# pdbV2_0.net
KiCad netlist of a schematic drawn in EAGLE
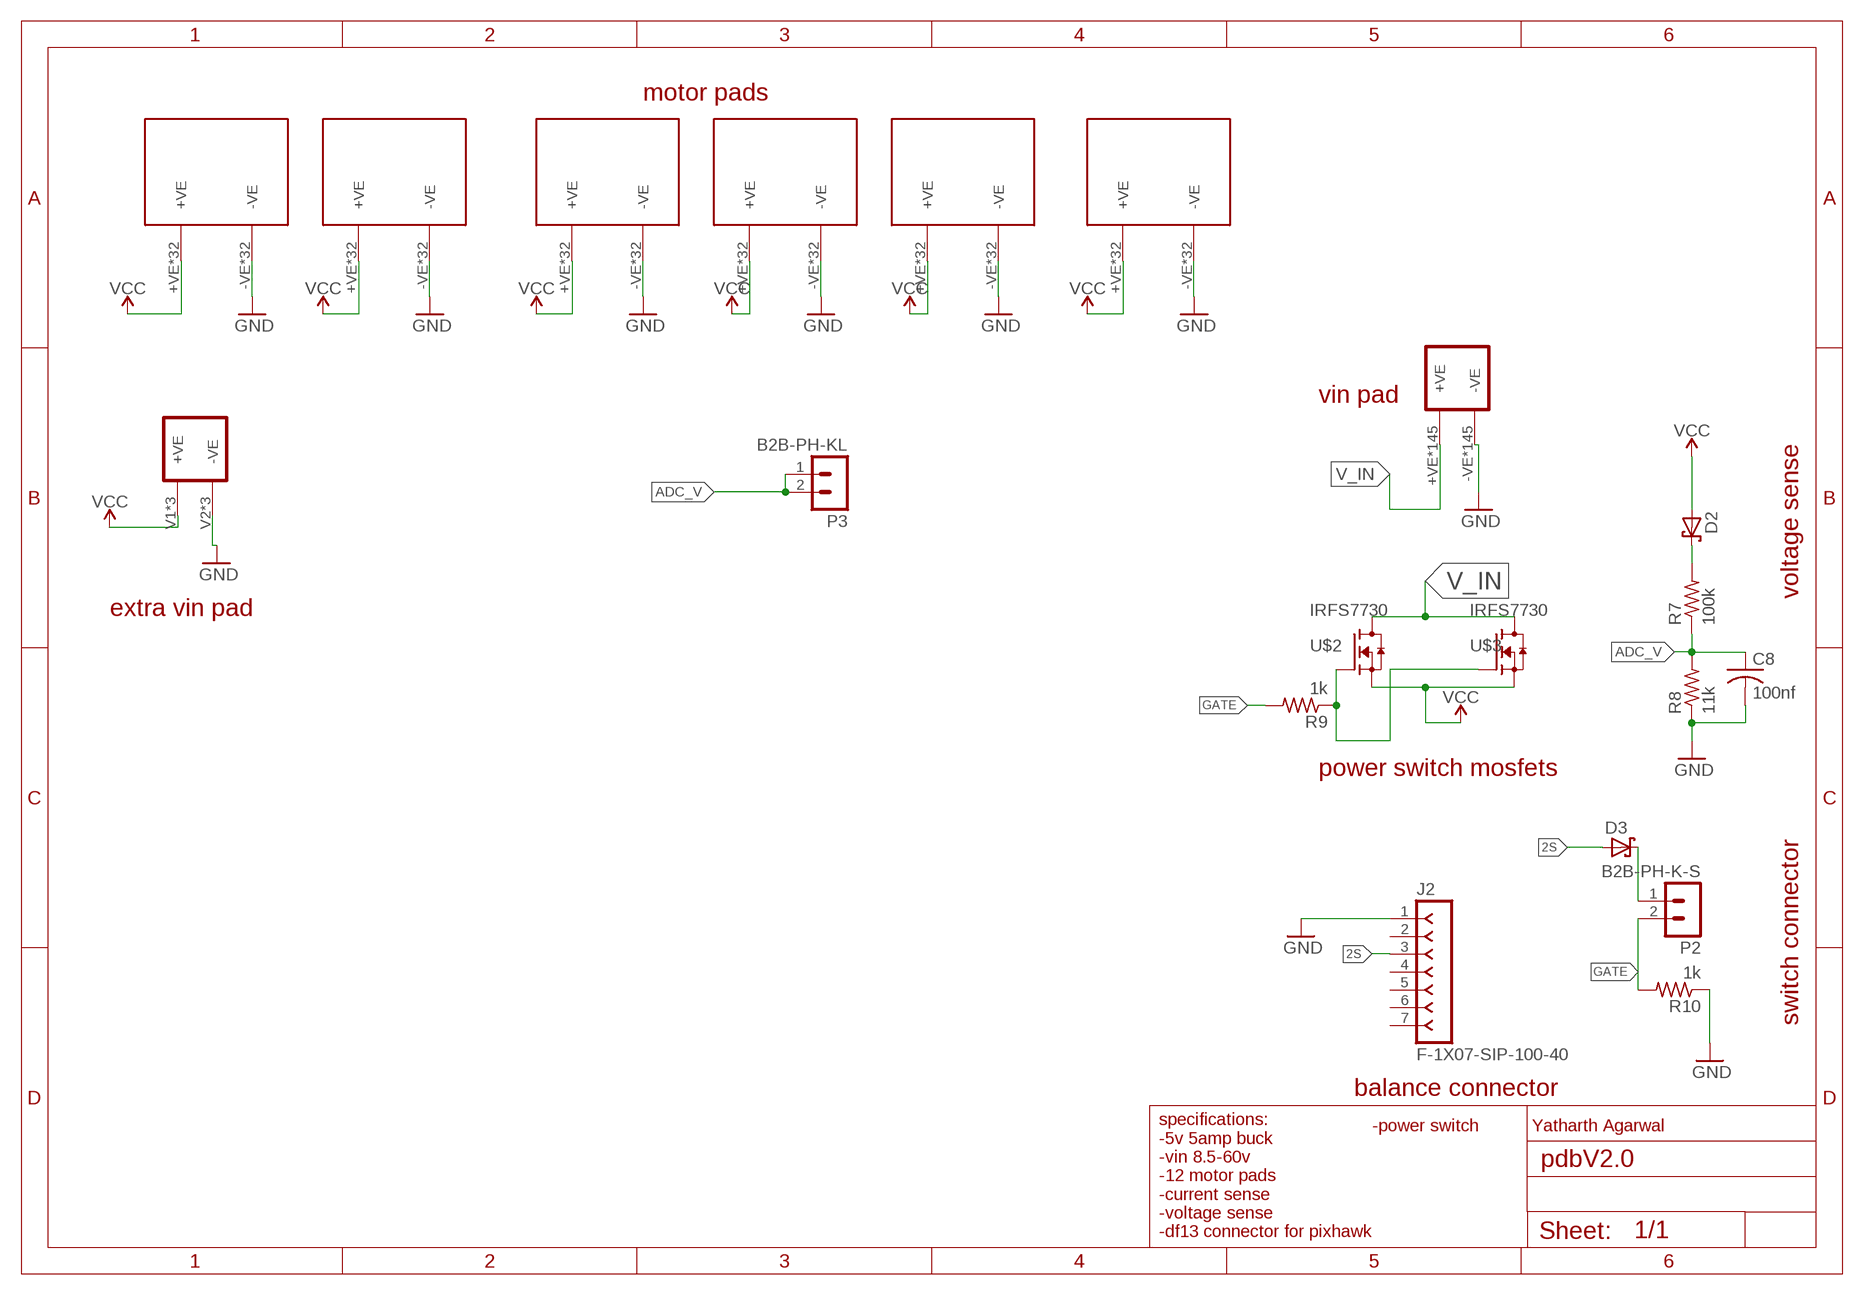
[diagram p0: schematic, sheet 1]

(export (version "E")
  (design (tool "Eeschema 10.0.6"))
  (components
    (comp (ref "C8")
      (value "100nf")
      (footprint "eagle-import:C0805")
      (libsource (lib "eagle-import") (part "C-USC0805"))
    )
    (comp (ref "D2")
      (value "1PS76SB70,115")
      (footprint "eagle-import:SOD323(F)")
      (fields (field (name "MF") "Nexperia USA"))
      (libsource (lib "eagle-import") (part "1PS76SB70,115"))
    )
    (comp (ref "D3")
      (value "1PS76SB70,115")
      (footprint "eagle-import:SOD323(F)")
      (fields (field (name "MF") "Nexperia USA"))
      (libsource (lib "eagle-import") (part "1PS76SB70,115"))
    )
    (comp (ref "J2")
      (value "F-1X07-SIP-100-40")
      (footprint "eagle-import:SIP-100-07-40")
      (libsource (lib "eagle-import") (part "F-1X07-SIP-100-40"))
    )
    (comp (ref "P2")
      (value "B2B-PH-K-S")
      (footprint "eagle-import:B2B-PH-K-S")
      (libsource (lib "eagle-import") (part "B2B-PH-K-S"))
    )
    (comp (ref "P3")
      (value "B2B-PH-KL")
      (footprint "eagle-import:B2B-PH-K-S")
      (libsource (lib "eagle-import") (part "B2B-PH-KL"))
    )
    (comp (ref "R7")
      (value "100k")
      (footprint "eagle-import:R0805")
      (libsource (lib "eagle-import") (part "R-US_R0805"))
    )
    (comp (ref "R8")
      (value "11k")
      (footprint "eagle-import:R0805")
      (libsource (lib "eagle-import") (part "R-US_R0805"))
    )
    (comp (ref "R9")
      (value "1k")
      (footprint "eagle-import:R0805")
      (libsource (lib "eagle-import") (part "R-US_R0805"))
    )
    (comp (ref "R10")
      (value "1k")
      (footprint "eagle-import:R0805")
      (libsource (lib "eagle-import") (part "R-US_R0805"))
    )
    (comp (ref "T1")
      (value "BATTERY_PAD")
      (footprint "eagle-import:BATTERY_PAD")
      (libsource (lib "eagle-import") (part "BATTERY_PAD"))
    )
    (comp (ref "T2")
      (value "MOTOR_PAD")
      (footprint "eagle-import:MOTOR_PAD")
      (libsource (lib "eagle-import") (part "MOTOR_PAD"))
    )
    (comp (ref "T3")
      (value "MOTOR_PAD")
      (footprint "eagle-import:MOTOR_PAD")
      (libsource (lib "eagle-import") (part "MOTOR_PAD"))
    )
    (comp (ref "T4")
      (value "MOTOR_PAD")
      (footprint "eagle-import:MOTOR_PAD")
      (libsource (lib "eagle-import") (part "MOTOR_PAD"))
    )
    (comp (ref "T5")
      (value "MOTOR_PAD")
      (footprint "eagle-import:MOTOR_PAD")
      (libsource (lib "eagle-import") (part "MOTOR_PAD"))
    )
    (comp (ref "T6")
      (value "MOTOR_PAD")
      (footprint "eagle-import:MOTOR_PAD")
      (libsource (lib "eagle-import") (part "MOTOR_PAD"))
    )
    (comp (ref "T7")
      (value "MOTOR_PAD")
      (footprint "eagle-import:MOTOR_PAD")
      (libsource (lib "eagle-import") (part "MOTOR_PAD"))
    )
    (comp (ref "U$1")
      (value "CONPAD")
      (footprint "eagle-import:CONPAD")
      (libsource (lib "eagle-import") (part "CONPAD"))
    )
    (comp (ref "U$2")
      (value "IRFS7730")
      (footprint "eagle-import:TO254P1524X457-3N")
      (libsource (lib "eagle-import") (part "IRFS7730"))
    )
    (comp (ref "U$3")
      (value "IRFS7730")
      (footprint "eagle-import:TO254P1524X457-3N")
      (libsource (lib "eagle-import") (part "IRFS7730"))
    )
  )
  (nets
    (net (code "1") (name "2S") (class "Default")
      (node (ref "D3") (pin "2") (pinfunction "A_2") (pintype "passive"))
      (node (ref "J2") (pin "3") (pinfunction "3_3") (pintype "passive"))
    )
    (net (code "2") (name "ADC_V") (class "Default")
      (node (ref "C8") (pin "1") (pinfunction "1_1") (pintype "passive"))
      (node (ref "P3") (pin "1") (pinfunction "1_1") (pintype "passive"))
      (node (ref "P3") (pin "2") (pinfunction "2_2") (pintype "passive"))
      (node (ref "R7") (pin "1") (pinfunction "1_1") (pintype "passive"))
      (node (ref "R8") (pin "2") (pinfunction "2_2") (pintype "passive"))
    )
    (net (code "3") (name "GATE") (class "Default")
      (node (ref "P2") (pin "2") (pinfunction "2_2") (pintype "passive"))
      (node (ref "R10") (pin "2") (pinfunction "2_2") (pintype "passive"))
      (node (ref "R9") (pin "2") (pinfunction "2_2") (pintype "passive"))
    )
    (net (code "4") (name "GND") (class "Default")
      (node (ref "C8") (pin "2") (pinfunction "2_2") (pintype "passive"))
      (node (ref "J2") (pin "1") (pinfunction "1_1") (pintype "passive"))
      (node (ref "R10") (pin "1") (pinfunction "1_1") (pintype "passive"))
      (node (ref "R8") (pin "1") (pinfunction "1_1") (pintype "passive"))
      (node (ref "T1") (pin "-VE") (pinfunction "-VE_-VE") (pintype "bidirectional"))
      (node (ref "T1") (pin "-VE_1") (pinfunction "-VE_-VE_1") (pintype "bidirectional"))
      (node (ref "T1") (pin "V109") (pinfunction "-VE_V109") (pintype "bidirectional"))
      (node (ref "T1") (pin "V110") (pinfunction "-VE_V110") (pintype "bidirectional"))
      (node (ref "T1") (pin "V111") (pinfunction "-VE_V111") (pintype "bidirectional"))
      (node (ref "T1") (pin "V112") (pinfunction "-VE_V112") (pintype "bidirectional"))
      (node (ref "T1") (pin "V113") (pinfunction "-VE_V113") (pintype "bidirectional"))
      (node (ref "T1") (pin "V114") (pinfunction "-VE_V114") (pintype "bidirectional"))
      (node (ref "T1") (pin "V115") (pinfunction "-VE_V115") (pintype "bidirectional"))
      (node (ref "T1") (pin "V116") (pinfunction "-VE_V116") (pintype "bidirectional"))
      (node (ref "T1") (pin "V117") (pinfunction "-VE_V117") (pintype "bidirectional"))
      (node (ref "T1") (pin "V118") (pinfunction "-VE_V118") (pintype "bidirectional"))
      (node (ref "T1") (pin "V119") (pinfunction "-VE_V119") (pintype "bidirectional"))
      (node (ref "T1") (pin "V121") (pinfunction "-VE_V121") (pintype "bidirectional"))
      (node (ref "T1") (pin "V122") (pinfunction "-VE_V122") (pintype "bidirectional"))
      (node (ref "T1") (pin "V123") (pinfunction "-VE_V123") (pintype "bidirectional"))
      (node (ref "T1") (pin "V124") (pinfunction "-VE_V124") (pintype "bidirectional"))
      (node (ref "T1") (pin "V125") (pinfunction "-VE_V125") (pintype "bidirectional"))
      (node (ref "T1") (pin "V126") (pinfunction "-VE_V126") (pintype "bidirectional"))
      (node (ref "T1") (pin "V127") (pinfunction "-VE_V127") (pintype "bidirectional"))
      (node (ref "T1") (pin "V128") (pinfunction "-VE_V128") (pintype "bidirectional"))
      (node (ref "T1") (pin "V129") (pinfunction "-VE_V129") (pintype "bidirectional"))
      (node (ref "T1") (pin "V130") (pinfunction "-VE_V130") (pintype "bidirectional"))
      (node (ref "T1") (pin "V131") (pinfunction "-VE_V131") (pintype "bidirectional"))
      (node (ref "T1") (pin "V133") (pinfunction "-VE_V133") (pintype "bidirectional"))
      (node (ref "T1") (pin "V134") (pinfunction "-VE_V134") (pintype "bidirectional"))
      (node (ref "T1") (pin "V135") (pinfunction "-VE_V135") (pintype "bidirectional"))
      (node (ref "T1") (pin "V136") (pinfunction "-VE_V136") (pintype "bidirectional"))
      (node (ref "T1") (pin "V137") (pinfunction "-VE_V137") (pintype "bidirectional"))
      (node (ref "T1") (pin "V138") (pinfunction "-VE_V138") (pintype "bidirectional"))
      (node (ref "T1") (pin "V139") (pinfunction "-VE_V139") (pintype "bidirectional"))
      (node (ref "T1") (pin "V140") (pinfunction "-VE_V140") (pintype "bidirectional"))
      (node (ref "T1") (pin "V141") (pinfunction "-VE_V141") (pintype "bidirectional"))
      (node (ref "T1") (pin "V142") (pinfunction "-VE_V142") (pintype "bidirectional"))
      (node (ref "T1") (pin "V143") (pinfunction "-VE_V143") (pintype "bidirectional"))
      (node (ref "T1") (pin "V145") (pinfunction "-VE_V145") (pintype "bidirectional"))
      (node (ref "T1") (pin "V146") (pinfunction "-VE_V146") (pintype "bidirectional"))
      (node (ref "T1") (pin "V147") (pinfunction "-VE_V147") (pintype "bidirectional"))
      (node (ref "T1") (pin "V148") (pinfunction "-VE_V148") (pintype "bidirectional"))
      (node (ref "T1") (pin "V149") (pinfunction "-VE_V149") (pintype "bidirectional"))
      (node (ref "T1") (pin "V150") (pinfunction "-VE_V150") (pintype "bidirectional"))
      (node (ref "T1") (pin "V151") (pinfunction "-VE_V151") (pintype "bidirectional"))
      (node (ref "T1") (pin "V152") (pinfunction "-VE_V152") (pintype "bidirectional"))
      (node (ref "T1") (pin "V153") (pinfunction "-VE_V153") (pintype "bidirectional"))
      (node (ref "T1") (pin "V154") (pinfunction "-VE_V154") (pintype "bidirectional"))
      (node (ref "T1") (pin "V155") (pinfunction "-VE_V155") (pintype "bidirectional"))
      (node (ref "T1") (pin "V157") (pinfunction "-VE_V157") (pintype "bidirectional"))
      (node (ref "T1") (pin "V158") (pinfunction "-VE_V158") (pintype "bidirectional"))
      (node (ref "T1") (pin "V159") (pinfunction "-VE_V159") (pintype "bidirectional"))
      (node (ref "T1") (pin "V160") (pinfunction "-VE_V160") (pintype "bidirectional"))
      (node (ref "T1") (pin "V161") (pinfunction "-VE_V161") (pintype "bidirectional"))
      (node (ref "T1") (pin "V162") (pinfunction "-VE_V162") (pintype "bidirectional"))
      (node (ref "T1") (pin "V163") (pinfunction "-VE_V163") (pintype "bidirectional"))
      (node (ref "T1") (pin "V164") (pinfunction "-VE_V164") (pintype "bidirectional"))
      (node (ref "T1") (pin "V165") (pinfunction "-VE_V165") (pintype "bidirectional"))
      (node (ref "T1") (pin "V166") (pinfunction "-VE_V166") (pintype "bidirectional"))
      (node (ref "T1") (pin "V167") (pinfunction "-VE_V167") (pintype "bidirectional"))
      (node (ref "T1") (pin "V169") (pinfunction "-VE_V169") (pintype "bidirectional"))
      (node (ref "T1") (pin "V170") (pinfunction "-VE_V170") (pintype "bidirectional"))
      (node (ref "T1") (pin "V171") (pinfunction "-VE_V171") (pintype "bidirectional"))
      (node (ref "T1") (pin "V172") (pinfunction "-VE_V172") (pintype "bidirectional"))
      (node (ref "T1") (pin "V173") (pinfunction "-VE_V173") (pintype "bidirectional"))
      (node (ref "T1") (pin "V174") (pinfunction "-VE_V174") (pintype "bidirectional"))
      (node (ref "T1") (pin "V175") (pinfunction "-VE_V175") (pintype "bidirectional"))
      (node (ref "T1") (pin "V176") (pinfunction "-VE_V176") (pintype "bidirectional"))
      (node (ref "T1") (pin "V177") (pinfunction "-VE_V177") (pintype "bidirectional"))
      (node (ref "T1") (pin "V178") (pinfunction "-VE_V178") (pintype "bidirectional"))
      (node (ref "T1") (pin "V179") (pinfunction "-VE_V179") (pintype "bidirectional"))
      (node (ref "T1") (pin "V181") (pinfunction "-VE_V181") (pintype "bidirectional"))
      (node (ref "T1") (pin "V182") (pinfunction "-VE_V182") (pintype "bidirectional"))
      (node (ref "T1") (pin "V183") (pinfunction "-VE_V183") (pintype "bidirectional"))
      (node (ref "T1") (pin "V184") (pinfunction "-VE_V184") (pintype "bidirectional"))
      (node (ref "T1") (pin "V185") (pinfunction "-VE_V185") (pintype "bidirectional"))
      (node (ref "T1") (pin "V186") (pinfunction "-VE_V186") (pintype "bidirectional"))
      (node (ref "T1") (pin "V187") (pinfunction "-VE_V187") (pintype "bidirectional"))
      (node (ref "T1") (pin "V188") (pinfunction "-VE_V188") (pintype "bidirectional"))
      (node (ref "T1") (pin "V189") (pinfunction "-VE_V189") (pintype "bidirectional"))
      (node (ref "T1") (pin "V190") (pinfunction "-VE_V190") (pintype "bidirectional"))
      (node (ref "T1") (pin "V191") (pinfunction "-VE_V191") (pintype "bidirectional"))
      (node (ref "T1") (pin "V193") (pinfunction "-VE_V193") (pintype "bidirectional"))
      (node (ref "T1") (pin "V194") (pinfunction "-VE_V194") (pintype "bidirectional"))
      (node (ref "T1") (pin "V195") (pinfunction "-VE_V195") (pintype "bidirectional"))
      (node (ref "T1") (pin "V196") (pinfunction "-VE_V196") (pintype "bidirectional"))
      (node (ref "T1") (pin "V197") (pinfunction "-VE_V197") (pintype "bidirectional"))
      (node (ref "T1") (pin "V198") (pinfunction "-VE_V198") (pintype "bidirectional"))
      (node (ref "T1") (pin "V199") (pinfunction "-VE_V199") (pintype "bidirectional"))
      (node (ref "T1") (pin "V200") (pinfunction "-VE_V200") (pintype "bidirectional"))
      (node (ref "T1") (pin "V201") (pinfunction "-VE_V201") (pintype "bidirectional"))
      (node (ref "T1") (pin "V202") (pinfunction "-VE_V202") (pintype "bidirectional"))
      (node (ref "T1") (pin "V203") (pinfunction "-VE_V203") (pintype "bidirectional"))
      (node (ref "T1") (pin "V232") (pinfunction "-VE_V232") (pintype "bidirectional"))
      (node (ref "T1") (pin "V233") (pinfunction "-VE_V233") (pintype "bidirectional"))
      (node (ref "T1") (pin "V234") (pinfunction "-VE_V234") (pintype "bidirectional"))
      (node (ref "T1") (pin "V235") (pinfunction "-VE_V235") (pintype "bidirectional"))
      (node (ref "T1") (pin "V236") (pinfunction "-VE_V236") (pintype "bidirectional"))
      (node (ref "T1") (pin "V237") (pinfunction "-VE_V237") (pintype "bidirectional"))
      (node (ref "T1") (pin "V238") (pinfunction "-VE_V238") (pintype "bidirectional"))
      (node (ref "T1") (pin "V239") (pinfunction "-VE_V239") (pintype "bidirectional"))
      (node (ref "T1") (pin "V240") (pinfunction "-VE_V240") (pintype "bidirectional"))
      (node (ref "T1") (pin "V241") (pinfunction "-VE_V241") (pintype "bidirectional"))
      (node (ref "T1") (pin "V242") (pinfunction "-VE_V242") (pintype "bidirectional"))
      (node (ref "T1") (pin "V243") (pinfunction "-VE_V243") (pintype "bidirectional"))
      (node (ref "T1") (pin "V244") (pinfunction "-VE_V244") (pintype "bidirectional"))
      (node (ref "T1") (pin "V245") (pinfunction "-VE_V245") (pintype "bidirectional"))
      (node (ref "T1") (pin "V246") (pinfunction "-VE_V246") (pintype "bidirectional"))
      (node (ref "T1") (pin "V247") (pinfunction "-VE_V247") (pintype "bidirectional"))
      (node (ref "T1") (pin "V248") (pinfunction "-VE_V248") (pintype "bidirectional"))
      (node (ref "T1") (pin "V249") (pinfunction "-VE_V249") (pintype "bidirectional"))
      (node (ref "T1") (pin "V250") (pinfunction "-VE_V250") (pintype "bidirectional"))
      (node (ref "T1") (pin "V251") (pinfunction "-VE_V251") (pintype "bidirectional"))
      (node (ref "T1") (pin "V252") (pinfunction "-VE_V252") (pintype "bidirectional"))
      (node (ref "T1") (pin "V253") (pinfunction "-VE_V253") (pintype "bidirectional"))
      (node (ref "T1") (pin "V254") (pinfunction "-VE_V254") (pintype "bidirectional"))
      (node (ref "T1") (pin "V255") (pinfunction "-VE_V255") (pintype "bidirectional"))
      (node (ref "T1") (pin "V256") (pinfunction "-VE_V256") (pintype "bidirectional"))
      (node (ref "T1") (pin "V257") (pinfunction "-VE_V257") (pintype "bidirectional"))
      (node (ref "T1") (pin "V258") (pinfunction "-VE_V258") (pintype "bidirectional"))
      (node (ref "T1") (pin "V259") (pinfunction "-VE_V259") (pintype "bidirectional"))
      (node (ref "T1") (pin "V260") (pinfunction "-VE_V260") (pintype "bidirectional"))
      (node (ref "T1") (pin "V261") (pinfunction "-VE_V261") (pintype "bidirectional"))
      (node (ref "T1") (pin "V262") (pinfunction "-VE_V262") (pintype "bidirectional"))
      (node (ref "T1") (pin "V263") (pinfunction "-VE_V263") (pintype "bidirectional"))
      (node (ref "T1") (pin "V264") (pinfunction "-VE_V264") (pintype "bidirectional"))
      (node (ref "T1") (pin "V265") (pinfunction "-VE_V265") (pintype "bidirectional"))
      (node (ref "T1") (pin "V266") (pinfunction "-VE_V266") (pintype "bidirectional"))
      (node (ref "T1") (pin "V267") (pinfunction "-VE_V267") (pintype "bidirectional"))
      (node (ref "T1") (pin "V268") (pinfunction "-VE_V268") (pintype "bidirectional"))
      (node (ref "T1") (pin "V269") (pinfunction "-VE_V269") (pintype "bidirectional"))
      (node (ref "T1") (pin "V270") (pinfunction "-VE_V270") (pintype "bidirectional"))
      (node (ref "T1") (pin "V271") (pinfunction "-VE_V271") (pintype "bidirectional"))
      (node (ref "T1") (pin "V272") (pinfunction "-VE_V272") (pintype "bidirectional"))
      (node (ref "T1") (pin "V273") (pinfunction "-VE_V273") (pintype "bidirectional"))
      (node (ref "T1") (pin "V274") (pinfunction "-VE_V274") (pintype "bidirectional"))
      (node (ref "T1") (pin "V275") (pinfunction "-VE_V275") (pintype "bidirectional"))
      (node (ref "T1") (pin "V276") (pinfunction "-VE_V276") (pintype "bidirectional"))
      (node (ref "T1") (pin "V277") (pinfunction "-VE_V277") (pintype "bidirectional"))
      (node (ref "T1") (pin "V278") (pinfunction "-VE_V278") (pintype "bidirectional"))
      (node (ref "T1") (pin "V279") (pinfunction "-VE_V279") (pintype "bidirectional"))
      (node (ref "T1") (pin "V280") (pinfunction "-VE_V280") (pintype "bidirectional"))
      (node (ref "T1") (pin "V281") (pinfunction "-VE_V281") (pintype "bidirectional"))
      (node (ref "T1") (pin "V282") (pinfunction "-VE_V282") (pintype "bidirectional"))
      (node (ref "T1") (pin "V283") (pinfunction "-VE_V283") (pintype "bidirectional"))
      (node (ref "T1") (pin "V284") (pinfunction "-VE_V284") (pintype "bidirectional"))
      (node (ref "T1") (pin "V285") (pinfunction "-VE_V285") (pintype "bidirectional"))
      (node (ref "T1") (pin "V286") (pinfunction "-VE_V286") (pintype "bidirectional"))
      (node (ref "T2") (pin "-VE") (pinfunction "-VE_-VE") (pintype "output"))
      (node (ref "T2") (pin "-VE_1") (pinfunction "-VE_-VE_1") (pintype "output"))
      (node (ref "T2") (pin "V32") (pinfunction "-VE_V32") (pintype "output"))
      (node (ref "T2") (pin "V33") (pinfunction "-VE_V33") (pintype "output"))
      (node (ref "T2") (pin "V34") (pinfunction "-VE_V34") (pintype "output"))
      (node (ref "T2") (pin "V35") (pinfunction "-VE_V35") (pintype "output"))
      (node (ref "T2") (pin "V36") (pinfunction "-VE_V36") (pintype "output"))
      (node (ref "T2") (pin "V37") (pinfunction "-VE_V37") (pintype "output"))
      (node (ref "T2") (pin "V38") (pinfunction "-VE_V38") (pintype "output"))
      (node (ref "T2") (pin "V39") (pinfunction "-VE_V39") (pintype "output"))
      (node (ref "T2") (pin "V40") (pinfunction "-VE_V40") (pintype "output"))
      (node (ref "T2") (pin "V41") (pinfunction "-VE_V41") (pintype "output"))
      (node (ref "T2") (pin "V42") (pinfunction "-VE_V42") (pintype "output"))
      (node (ref "T2") (pin "V43") (pinfunction "-VE_V43") (pintype "output"))
      (node (ref "T2") (pin "V44") (pinfunction "-VE_V44") (pintype "output"))
      (node (ref "T2") (pin "V45") (pinfunction "-VE_V45") (pintype "output"))
      (node (ref "T2") (pin "V46") (pinfunction "-VE_V46") (pintype "output"))
      (node (ref "T2") (pin "V47") (pinfunction "-VE_V47") (pintype "output"))
      (node (ref "T2") (pin "V48") (pinfunction "-VE_V48") (pintype "output"))
      (node (ref "T2") (pin "V49") (pinfunction "-VE_V49") (pintype "output"))
      (node (ref "T2") (pin "V50") (pinfunction "-VE_V50") (pintype "output"))
      (node (ref "T2") (pin "V51") (pinfunction "-VE_V51") (pintype "output"))
      (node (ref "T2") (pin "V52") (pinfunction "-VE_V52") (pintype "output"))
      (node (ref "T2") (pin "V53") (pinfunction "-VE_V53") (pintype "output"))
      (node (ref "T2") (pin "V54") (pinfunction "-VE_V54") (pintype "output"))
      (node (ref "T2") (pin "V55") (pinfunction "-VE_V55") (pintype "output"))
      (node (ref "T2") (pin "V56") (pinfunction "-VE_V56") (pintype "output"))
      (node (ref "T2") (pin "V57") (pinfunction "-VE_V57") (pintype "output"))
      (node (ref "T2") (pin "V58") (pinfunction "-VE_V58") (pintype "output"))
      (node (ref "T2") (pin "V59") (pinfunction "-VE_V59") (pintype "output"))
      (node (ref "T2") (pin "V60") (pinfunction "-VE_V60") (pintype "output"))
      (node (ref "T2") (pin "V61") (pinfunction "-VE_V61") (pintype "output"))
      (node (ref "T3") (pin "-VE") (pinfunction "-VE_-VE") (pintype "output"))
      (node (ref "T3") (pin "-VE_1") (pinfunction "-VE_-VE_1") (pintype "output"))
      (node (ref "T3") (pin "V32") (pinfunction "-VE_V32") (pintype "output"))
      (node (ref "T3") (pin "V33") (pinfunction "-VE_V33") (pintype "output"))
      (node (ref "T3") (pin "V34") (pinfunction "-VE_V34") (pintype "output"))
      (node (ref "T3") (pin "V35") (pinfunction "-VE_V35") (pintype "output"))
      (node (ref "T3") (pin "V36") (pinfunction "-VE_V36") (pintype "output"))
      (node (ref "T3") (pin "V37") (pinfunction "-VE_V37") (pintype "output"))
      (node (ref "T3") (pin "V38") (pinfunction "-VE_V38") (pintype "output"))
      (node (ref "T3") (pin "V39") (pinfunction "-VE_V39") (pintype "output"))
      (node (ref "T3") (pin "V40") (pinfunction "-VE_V40") (pintype "output"))
      (node (ref "T3") (pin "V41") (pinfunction "-VE_V41") (pintype "output"))
      (node (ref "T3") (pin "V42") (pinfunction "-VE_V42") (pintype "output"))
      (node (ref "T3") (pin "V43") (pinfunction "-VE_V43") (pintype "output"))
      (node (ref "T3") (pin "V44") (pinfunction "-VE_V44") (pintype "output"))
      (node (ref "T3") (pin "V45") (pinfunction "-VE_V45") (pintype "output"))
      (node (ref "T3") (pin "V46") (pinfunction "-VE_V46") (pintype "output"))
      (node (ref "T3") (pin "V47") (pinfunction "-VE_V47") (pintype "output"))
      (node (ref "T3") (pin "V48") (pinfunction "-VE_V48") (pintype "output"))
      (node (ref "T3") (pin "V49") (pinfunction "-VE_V49") (pintype "output"))
      (node (ref "T3") (pin "V50") (pinfunction "-VE_V50") (pintype "output"))
      (node (ref "T3") (pin "V51") (pinfunction "-VE_V51") (pintype "output"))
      (node (ref "T3") (pin "V52") (pinfunction "-VE_V52") (pintype "output"))
      (node (ref "T3") (pin "V53") (pinfunction "-VE_V53") (pintype "output"))
      (node (ref "T3") (pin "V54") (pinfunction "-VE_V54") (pintype "output"))
      (node (ref "T3") (pin "V55") (pinfunction "-VE_V55") (pintype "output"))
      (node (ref "T3") (pin "V56") (pinfunction "-VE_V56") (pintype "output"))
      (node (ref "T3") (pin "V57") (pinfunction "-VE_V57") (pintype "output"))
      (node (ref "T3") (pin "V58") (pinfunction "-VE_V58") (pintype "output"))
      (node (ref "T3") (pin "V59") (pinfunction "-VE_V59") (pintype "output"))
      (node (ref "T3") (pin "V60") (pinfunction "-VE_V60") (pintype "output"))
      (node (ref "T3") (pin "V61") (pinfunction "-VE_V61") (pintype "output"))
      (node (ref "T4") (pin "-VE") (pinfunction "-VE_-VE") (pintype "output"))
      (node (ref "T4") (pin "-VE_1") (pinfunction "-VE_-VE_1") (pintype "output"))
      (node (ref "T4") (pin "V32") (pinfunction "-VE_V32") (pintype "output"))
      (node (ref "T4") (pin "V33") (pinfunction "-VE_V33") (pintype "output"))
      (node (ref "T4") (pin "V34") (pinfunction "-VE_V34") (pintype "output"))
      (node (ref "T4") (pin "V35") (pinfunction "-VE_V35") (pintype "output"))
      (node (ref "T4") (pin "V36") (pinfunction "-VE_V36") (pintype "output"))
      (node (ref "T4") (pin "V37") (pinfunction "-VE_V37") (pintype "output"))
      (node (ref "T4") (pin "V38") (pinfunction "-VE_V38") (pintype "output"))
      (node (ref "T4") (pin "V39") (pinfunction "-VE_V39") (pintype "output"))
      (node (ref "T4") (pin "V40") (pinfunction "-VE_V40") (pintype "output"))
      (node (ref "T4") (pin "V41") (pinfunction "-VE_V41") (pintype "output"))
      (node (ref "T4") (pin "V42") (pinfunction "-VE_V42") (pintype "output"))
      (node (ref "T4") (pin "V43") (pinfunction "-VE_V43") (pintype "output"))
      (node (ref "T4") (pin "V44") (pinfunction "-VE_V44") (pintype "output"))
      (node (ref "T4") (pin "V45") (pinfunction "-VE_V45") (pintype "output"))
      (node (ref "T4") (pin "V46") (pinfunction "-VE_V46") (pintype "output"))
      (node (ref "T4") (pin "V47") (pinfunction "-VE_V47") (pintype "output"))
      (node (ref "T4") (pin "V48") (pinfunction "-VE_V48") (pintype "output"))
      (node (ref "T4") (pin "V49") (pinfunction "-VE_V49") (pintype "output"))
      (node (ref "T4") (pin "V50") (pinfunction "-VE_V50") (pintype "output"))
      (node (ref "T4") (pin "V51") (pinfunction "-VE_V51") (pintype "output"))
      (node (ref "T4") (pin "V52") (pinfunction "-VE_V52") (pintype "output"))
      (node (ref "T4") (pin "V53") (pinfunction "-VE_V53") (pintype "output"))
      (node (ref "T4") (pin "V54") (pinfunction "-VE_V54") (pintype "output"))
      (node (ref "T4") (pin "V55") (pinfunction "-VE_V55") (pintype "output"))
      (node (ref "T4") (pin "V56") (pinfunction "-VE_V56") (pintype "output"))
      (node (ref "T4") (pin "V57") (pinfunction "-VE_V57") (pintype "output"))
      (node (ref "T4") (pin "V58") (pinfunction "-VE_V58") (pintype "output"))
      (node (ref "T4") (pin "V59") (pinfunction "-VE_V59") (pintype "output"))
      (node (ref "T4") (pin "V60") (pinfunction "-VE_V60") (pintype "output"))
      (node (ref "T4") (pin "V61") (pinfunction "-VE_V61") (pintype "output"))
      (node (ref "T5") (pin "-VE") (pinfunction "-VE_-VE") (pintype "output"))
      (node (ref "T5") (pin "-VE_1") (pinfunction "-VE_-VE_1") (pintype "output"))
      (node (ref "T5") (pin "V32") (pinfunction "-VE_V32") (pintype "output"))
      (node (ref "T5") (pin "V33") (pinfunction "-VE_V33") (pintype "output"))
      (node (ref "T5") (pin "V34") (pinfunction "-VE_V34") (pintype "output"))
      (node (ref "T5") (pin "V35") (pinfunction "-VE_V35") (pintype "output"))
      (node (ref "T5") (pin "V36") (pinfunction "-VE_V36") (pintype "output"))
      (node (ref "T5") (pin "V37") (pinfunction "-VE_V37") (pintype "output"))
      (node (ref "T5") (pin "V38") (pinfunction "-VE_V38") (pintype "output"))
      (node (ref "T5") (pin "V39") (pinfunction "-VE_V39") (pintype "output"))
      (node (ref "T5") (pin "V40") (pinfunction "-VE_V40") (pintype "output"))
      (node (ref "T5") (pin "V41") (pinfunction "-VE_V41") (pintype "output"))
      (node (ref "T5") (pin "V42") (pinfunction "-VE_V42") (pintype "output"))
      (node (ref "T5") (pin "V43") (pinfunction "-VE_V43") (pintype "output"))
      (node (ref "T5") (pin "V44") (pinfunction "-VE_V44") (pintype "output"))
      (node (ref "T5") (pin "V45") (pinfunction "-VE_V45") (pintype "output"))
      (node (ref "T5") (pin "V46") (pinfunction "-VE_V46") (pintype "output"))
      (node (ref "T5") (pin "V47") (pinfunction "-VE_V47") (pintype "output"))
      (node (ref "T5") (pin "V48") (pinfunction "-VE_V48") (pintype "output"))
      (node (ref "T5") (pin "V49") (pinfunction "-VE_V49") (pintype "output"))
      (node (ref "T5") (pin "V50") (pinfunction "-VE_V50") (pintype "output"))
      (node (ref "T5") (pin "V51") (pinfunction "-VE_V51") (pintype "output"))
      (node (ref "T5") (pin "V52") (pinfunction "-VE_V52") (pintype "output"))
      (node (ref "T5") (pin "V53") (pinfunction "-VE_V53") (pintype "output"))
      (node (ref "T5") (pin "V54") (pinfunction "-VE_V54") (pintype "output"))
      (node (ref "T5") (pin "V55") (pinfunction "-VE_V55") (pintype "output"))
      (node (ref "T5") (pin "V56") (pinfunction "-VE_V56") (pintype "output"))
      (node (ref "T5") (pin "V57") (pinfunction "-VE_V57") (pintype "output"))
      (node (ref "T5") (pin "V58") (pinfunction "-VE_V58") (pintype "output"))
      (node (ref "T5") (pin "V59") (pinfunction "-VE_V59") (pintype "output"))
      (node (ref "T5") (pin "V60") (pinfunction "-VE_V60") (pintype "output"))
      (node (ref "T5") (pin "V61") (pinfunction "-VE_V61") (pintype "output"))
      (node (ref "T6") (pin "-VE") (pinfunction "-VE_-VE") (pintype "output"))
      (node (ref "T6") (pin "-VE_1") (pinfunction "-VE_-VE_1") (pintype "output"))
      (node (ref "T6") (pin "V32") (pinfunction "-VE_V32") (pintype "output"))
      (node (ref "T6") (pin "V33") (pinfunction "-VE_V33") (pintype "output"))
      (node (ref "T6") (pin "V34") (pinfunction "-VE_V34") (pintype "output"))
      (node (ref "T6") (pin "V35") (pinfunction "-VE_V35") (pintype "output"))
      (node (ref "T6") (pin "V36") (pinfunction "-VE_V36") (pintype "output"))
      (node (ref "T6") (pin "V37") (pinfunction "-VE_V37") (pintype "output"))
      (node (ref "T6") (pin "V38") (pinfunction "-VE_V38") (pintype "output"))
      (node (ref "T6") (pin "V39") (pinfunction "-VE_V39") (pintype "output"))
      (node (ref "T6") (pin "V40") (pinfunction "-VE_V40") (pintype "output"))
      (node (ref "T6") (pin "V41") (pinfunction "-VE_V41") (pintype "output"))
      (node (ref "T6") (pin "V42") (pinfunction "-VE_V42") (pintype "output"))
      (node (ref "T6") (pin "V43") (pinfunction "-VE_V43") (pintype "output"))
      (node (ref "T6") (pin "V44") (pinfunction "-VE_V44") (pintype "output"))
      (node (ref "T6") (pin "V45") (pinfunction "-VE_V45") (pintype "output"))
      (node (ref "T6") (pin "V46") (pinfunction "-VE_V46") (pintype "output"))
      (node (ref "T6") (pin "V47") (pinfunction "-VE_V47") (pintype "output"))
      (node (ref "T6") (pin "V48") (pinfunction "-VE_V48") (pintype "output"))
      (node (ref "T6") (pin "V49") (pinfunction "-VE_V49") (pintype "output"))
      (node (ref "T6") (pin "V50") (pinfunction "-VE_V50") (pintype "output"))
      (node (ref "T6") (pin "V51") (pinfunction "-VE_V51") (pintype "output"))
      (node (ref "T6") (pin "V52") (pinfunction "-VE_V52") (pintype "output"))
      (node (ref "T6") (pin "V53") (pinfunction "-VE_V53") (pintype "output"))
      (node (ref "T6") (pin "V54") (pinfunction "-VE_V54") (pintype "output"))
      (node (ref "T6") (pin "V55") (pinfunction "-VE_V55") (pintype "output"))
      (node (ref "T6") (pin "V56") (pinfunction "-VE_V56") (pintype "output"))
      (node (ref "T6") (pin "V57") (pinfunction "-VE_V57") (pintype "output"))
      (node (ref "T6") (pin "V58") (pinfunction "-VE_V58") (pintype "output"))
      (node (ref "T6") (pin "V59") (pinfunction "-VE_V59") (pintype "output"))
      (node (ref "T6") (pin "V60") (pinfunction "-VE_V60") (pintype "output"))
      (node (ref "T6") (pin "V61") (pinfunction "-VE_V61") (pintype "output"))
      (node (ref "T7") (pin "-VE") (pinfunction "-VE_-VE") (pintype "output"))
      (node (ref "T7") (pin "-VE_1") (pinfunction "-VE_-VE_1") (pintype "output"))
      (node (ref "T7") (pin "V32") (pinfunction "-VE_V32") (pintype "output"))
      (node (ref "T7") (pin "V33") (pinfunction "-VE_V33") (pintype "output"))
      (node (ref "T7") (pin "V34") (pinfunction "-VE_V34") (pintype "output"))
      (node (ref "T7") (pin "V35") (pinfunction "-VE_V35") (pintype "output"))
      (node (ref "T7") (pin "V36") (pinfunction "-VE_V36") (pintype "output"))
      (node (ref "T7") (pin "V37") (pinfunction "-VE_V37") (pintype "output"))
      (node (ref "T7") (pin "V38") (pinfunction "-VE_V38") (pintype "output"))
      (node (ref "T7") (pin "V39") (pinfunction "-VE_V39") (pintype "output"))
      (node (ref "T7") (pin "V40") (pinfunction "-VE_V40") (pintype "output"))
      (node (ref "T7") (pin "V41") (pinfunction "-VE_V41") (pintype "output"))
      (node (ref "T7") (pin "V42") (pinfunction "-VE_V42") (pintype "output"))
      (node (ref "T7") (pin "V43") (pinfunction "-VE_V43") (pintype "output"))
      (node (ref "T7") (pin "V44") (pinfunction "-VE_V44") (pintype "output"))
      (node (ref "T7") (pin "V45") (pinfunction "-VE_V45") (pintype "output"))
      (node (ref "T7") (pin "V46") (pinfunction "-VE_V46") (pintype "output"))
      (node (ref "T7") (pin "V47") (pinfunction "-VE_V47") (pintype "output"))
      (node (ref "T7") (pin "V48") (pinfunction "-VE_V48") (pintype "output"))
      (node (ref "T7") (pin "V49") (pinfunction "-VE_V49") (pintype "output"))
      (node (ref "T7") (pin "V50") (pinfunction "-VE_V50") (pintype "output"))
      (node (ref "T7") (pin "V51") (pinfunction "-VE_V51") (pintype "output"))
      (node (ref "T7") (pin "V52") (pinfunction "-VE_V52") (pintype "output"))
      (node (ref "T7") (pin "V53") (pinfunction "-VE_V53") (pintype "output"))
      (node (ref "T7") (pin "V54") (pinfunction "-VE_V54") (pintype "output"))
      (node (ref "T7") (pin "V55") (pinfunction "-VE_V55") (pintype "output"))
      (node (ref "T7") (pin "V56") (pinfunction "-VE_V56") (pintype "output"))
      (node (ref "T7") (pin "V57") (pinfunction "-VE_V57") (pintype "output"))
      (node (ref "T7") (pin "V58") (pinfunction "-VE_V58") (pintype "output"))
      (node (ref "T7") (pin "V59") (pinfunction "-VE_V59") (pintype "output"))
      (node (ref "T7") (pin "V60") (pinfunction "-VE_V60") (pintype "output"))
      (node (ref "T7") (pin "V61") (pinfunction "-VE_V61") (pintype "output"))
      (node (ref "U$1") (pin "V2") (pinfunction "-VE_V2") (pintype "bidirectional"))
      (node (ref "U$1") (pin "V4") (pinfunction "-VE_V4") (pintype "bidirectional"))
      (node (ref "U$1") (pin "V6") (pinfunction "-VE_V6") (pintype "bidirectional"))
    )
    (net (code "5") (name "Net-(D2-K)") (class "Default")
      (node (ref "D2") (pin "1") (pinfunction "K_1") (pintype "passive"))
      (node (ref "R7") (pin "2") (pinfunction "2_2") (pintype "passive"))
    )
    (net (code "6") (name "Net-(D3-K)") (class "Default")
      (node (ref "D3") (pin "1") (pinfunction "K_1") (pintype "passive"))
      (node (ref "P2") (pin "1") (pinfunction "1_1") (pintype "passive"))
    )
    (net (code "7") (name "Net-(U$2-G)") (class "Default")
      (node (ref "R9") (pin "1") (pinfunction "1_1") (pintype "passive"))
      (node (ref "U$2") (pin "1") (pinfunction "G_1") (pintype "passive"))
      (node (ref "U$3") (pin "1") (pinfunction "G_1") (pintype "passive"))
    )
    (net (code "8") (name "VCC") (class "Default")
      (node (ref "D2") (pin "2") (pinfunction "A_2") (pintype "passive"))
      (node (ref "T2") (pin "+VE") (pinfunction "+VE_+VE") (pintype "output"))
      (node (ref "T2") (pin "+VE_1") (pinfunction "+VE_+VE_1") (pintype "output"))
      (node (ref "T2") (pin "V1") (pinfunction "+VE_V1") (pintype "output"))
      (node (ref "T2") (pin "V10") (pinfunction "+VE_V10") (pintype "output"))
      (node (ref "T2") (pin "V11") (pinfunction "+VE_V11") (pintype "output"))
      (node (ref "T2") (pin "V12") (pinfunction "+VE_V12") (pintype "output"))
      (node (ref "T2") (pin "V13") (pinfunction "+VE_V13") (pintype "output"))
      (node (ref "T2") (pin "V14") (pinfunction "+VE_V14") (pintype "output"))
      (node (ref "T2") (pin "V15") (pinfunction "+VE_V15") (pintype "output"))
      (node (ref "T2") (pin "V16") (pinfunction "+VE_V16") (pintype "output"))
      (node (ref "T2") (pin "V17") (pinfunction "+VE_V17") (pintype "output"))
      (node (ref "T2") (pin "V18") (pinfunction "+VE_V18") (pintype "output"))
      (node (ref "T2") (pin "V19") (pinfunction "+VE_V19") (pintype "output"))
      (node (ref "T2") (pin "V20") (pinfunction "+VE_V20") (pintype "output"))
      (node (ref "T2") (pin "V21") (pinfunction "+VE_V21") (pintype "output"))
      (node (ref "T2") (pin "V22") (pinfunction "+VE_V22") (pintype "output"))
      (node (ref "T2") (pin "V23") (pinfunction "+VE_V23") (pintype "output"))
      (node (ref "T2") (pin "V24") (pinfunction "+VE_V24") (pintype "output"))
      (node (ref "T2") (pin "V25") (pinfunction "+VE_V25") (pintype "output"))
      (node (ref "T2") (pin "V26") (pinfunction "+VE_V26") (pintype "output"))
      (node (ref "T2") (pin "V27") (pinfunction "+VE_V27") (pintype "output"))
      (node (ref "T2") (pin "V28") (pinfunction "+VE_V28") (pintype "output"))
      (node (ref "T2") (pin "V29") (pinfunction "+VE_V29") (pintype "output"))
      (node (ref "T2") (pin "V3") (pinfunction "+VE_V3") (pintype "output"))
      (node (ref "T2") (pin "V30") (pinfunction "+VE_V30") (pintype "output"))
      (node (ref "T2") (pin "V31") (pinfunction "+VE_V31") (pintype "output"))
      (node (ref "T2") (pin "V4") (pinfunction "+VE_V4") (pintype "output"))
      (node (ref "T2") (pin "V5") (pinfunction "+VE_V5") (pintype "output"))
      (node (ref "T2") (pin "V6") (pinfunction "+VE_V6") (pintype "output"))
      (node (ref "T2") (pin "V7") (pinfunction "+VE_V7") (pintype "output"))
      (node (ref "T2") (pin "V8") (pinfunction "+VE_V8") (pintype "output"))
      (node (ref "T2") (pin "V9") (pinfunction "+VE_V9") (pintype "output"))
      (node (ref "T3") (pin "+VE") (pinfunction "+VE_+VE") (pintype "output"))
      (node (ref "T3") (pin "+VE_1") (pinfunction "+VE_+VE_1") (pintype "output"))
      (node (ref "T3") (pin "V1") (pinfunction "+VE_V1") (pintype "output"))
      (node (ref "T3") (pin "V10") (pinfunction "+VE_V10") (pintype "output"))
      (node (ref "T3") (pin "V11") (pinfunction "+VE_V11") (pintype "output"))
      (node (ref "T3") (pin "V12") (pinfunction "+VE_V12") (pintype "output"))
      (node (ref "T3") (pin "V13") (pinfunction "+VE_V13") (pintype "output"))
      (node (ref "T3") (pin "V14") (pinfunction "+VE_V14") (pintype "output"))
      (node (ref "T3") (pin "V15") (pinfunction "+VE_V15") (pintype "output"))
      (node (ref "T3") (pin "V16") (pinfunction "+VE_V16") (pintype "output"))
      (node (ref "T3") (pin "V17") (pinfunction "+VE_V17") (pintype "output"))
      (node (ref "T3") (pin "V18") (pinfunction "+VE_V18") (pintype "output"))
      (node (ref "T3") (pin "V19") (pinfunction "+VE_V19") (pintype "output"))
      (node (ref "T3") (pin "V20") (pinfunction "+VE_V20") (pintype "output"))
      (node (ref "T3") (pin "V21") (pinfunction "+VE_V21") (pintype "output"))
      (node (ref "T3") (pin "V22") (pinfunction "+VE_V22") (pintype "output"))
      (node (ref "T3") (pin "V23") (pinfunction "+VE_V23") (pintype "output"))
      (node (ref "T3") (pin "V24") (pinfunction "+VE_V24") (pintype "output"))
      (node (ref "T3") (pin "V25") (pinfunction "+VE_V25") (pintype "output"))
      (node (ref "T3") (pin "V26") (pinfunction "+VE_V26") (pintype "output"))
      (node (ref "T3") (pin "V27") (pinfunction "+VE_V27") (pintype "output"))
      (node (ref "T3") (pin "V28") (pinfunction "+VE_V28") (pintype "output"))
      (node (ref "T3") (pin "V29") (pinfunction "+VE_V29") (pintype "output"))
      (node (ref "T3") (pin "V3") (pinfunction "+VE_V3") (pintype "output"))
      (node (ref "T3") (pin "V30") (pinfunction "+VE_V30") (pintype "output"))
      (node (ref "T3") (pin "V31") (pinfunction "+VE_V31") (pintype "output"))
      (node (ref "T3") (pin "V4") (pinfunction "+VE_V4") (pintype "output"))
      (node (ref "T3") (pin "V5") (pinfunction "+VE_V5") (pintype "output"))
      (node (ref "T3") (pin "V6") (pinfunction "+VE_V6") (pintype "output"))
      (node (ref "T3") (pin "V7") (pinfunction "+VE_V7") (pintype "output"))
      (node (ref "T3") (pin "V8") (pinfunction "+VE_V8") (pintype "output"))
      (node (ref "T3") (pin "V9") (pinfunction "+VE_V9") (pintype "output"))
      (node (ref "T4") (pin "+VE") (pinfunction "+VE_+VE") (pintype "output"))
      (node (ref "T4") (pin "+VE_1") (pinfunction "+VE_+VE_1") (pintype "output"))
      (node (ref "T4") (pin "V1") (pinfunction "+VE_V1") (pintype "output"))
      (node (ref "T4") (pin "V10") (pinfunction "+VE_V10") (pintype "output"))
      (node (ref "T4") (pin "V11") (pinfunction "+VE_V11") (pintype "output"))
      (node (ref "T4") (pin "V12") (pinfunction "+VE_V12") (pintype "output"))
      (node (ref "T4") (pin "V13") (pinfunction "+VE_V13") (pintype "output"))
      (node (ref "T4") (pin "V14") (pinfunction "+VE_V14") (pintype "output"))
      (node (ref "T4") (pin "V15") (pinfunction "+VE_V15") (pintype "output"))
      (node (ref "T4") (pin "V16") (pinfunction "+VE_V16") (pintype "output"))
      (node (ref "T4") (pin "V17") (pinfunction "+VE_V17") (pintype "output"))
      (node (ref "T4") (pin "V18") (pinfunction "+VE_V18") (pintype "output"))
      (node (ref "T4") (pin "V19") (pinfunction "+VE_V19") (pintype "output"))
      (node (ref "T4") (pin "V20") (pinfunction "+VE_V20") (pintype "output"))
      (node (ref "T4") (pin "V21") (pinfunction "+VE_V21") (pintype "output"))
      (node (ref "T4") (pin "V22") (pinfunction "+VE_V22") (pintype "output"))
      (node (ref "T4") (pin "V23") (pinfunction "+VE_V23") (pintype "output"))
      (node (ref "T4") (pin "V24") (pinfunction "+VE_V24") (pintype "output"))
      (node (ref "T4") (pin "V25") (pinfunction "+VE_V25") (pintype "output"))
      (node (ref "T4") (pin "V26") (pinfunction "+VE_V26") (pintype "output"))
      (node (ref "T4") (pin "V27") (pinfunction "+VE_V27") (pintype "output"))
      (node (ref "T4") (pin "V28") (pinfunction "+VE_V28") (pintype "output"))
      (node (ref "T4") (pin "V29") (pinfunction "+VE_V29") (pintype "output"))
      (node (ref "T4") (pin "V3") (pinfunction "+VE_V3") (pintype "output"))
      (node (ref "T4") (pin "V30") (pinfunction "+VE_V30") (pintype "output"))
      (node (ref "T4") (pin "V31") (pinfunction "+VE_V31") (pintype "output"))
      (node (ref "T4") (pin "V4") (pinfunction "+VE_V4") (pintype "output"))
      (node (ref "T4") (pin "V5") (pinfunction "+VE_V5") (pintype "output"))
      (node (ref "T4") (pin "V6") (pinfunction "+VE_V6") (pintype "output"))
      (node (ref "T4") (pin "V7") (pinfunction "+VE_V7") (pintype "output"))
      (node (ref "T4") (pin "V8") (pinfunction "+VE_V8") (pintype "output"))
      (node (ref "T4") (pin "V9") (pinfunction "+VE_V9") (pintype "output"))
      (node (ref "T5") (pin "+VE") (pinfunction "+VE_+VE") (pintype "output"))
      (node (ref "T5") (pin "+VE_1") (pinfunction "+VE_+VE_1") (pintype "output"))
      (node (ref "T5") (pin "V1") (pinfunction "+VE_V1") (pintype "output"))
      (node (ref "T5") (pin "V10") (pinfunction "+VE_V10") (pintype "output"))
      (node (ref "T5") (pin "V11") (pinfunction "+VE_V11") (pintype "output"))
      (node (ref "T5") (pin "V12") (pinfunction "+VE_V12") (pintype "output"))
      (node (ref "T5") (pin "V13") (pinfunction "+VE_V13") (pintype "output"))
      (node (ref "T5") (pin "V14") (pinfunction "+VE_V14") (pintype "output"))
      (node (ref "T5") (pin "V15") (pinfunction "+VE_V15") (pintype "output"))
      (node (ref "T5") (pin "V16") (pinfunction "+VE_V16") (pintype "output"))
      (node (ref "T5") (pin "V17") (pinfunction "+VE_V17") (pintype "output"))
      (node (ref "T5") (pin "V18") (pinfunction "+VE_V18") (pintype "output"))
      (node (ref "T5") (pin "V19") (pinfunction "+VE_V19") (pintype "output"))
      (node (ref "T5") (pin "V20") (pinfunction "+VE_V20") (pintype "output"))
      (node (ref "T5") (pin "V21") (pinfunction "+VE_V21") (pintype "output"))
      (node (ref "T5") (pin "V22") (pinfunction "+VE_V22") (pintype "output"))
      (node (ref "T5") (pin "V23") (pinfunction "+VE_V23") (pintype "output"))
      (node (ref "T5") (pin "V24") (pinfunction "+VE_V24") (pintype "output"))
      (node (ref "T5") (pin "V25") (pinfunction "+VE_V25") (pintype "output"))
      (node (ref "T5") (pin "V26") (pinfunction "+VE_V26") (pintype "output"))
      (node (ref "T5") (pin "V27") (pinfunction "+VE_V27") (pintype "output"))
      (node (ref "T5") (pin "V28") (pinfunction "+VE_V28") (pintype "output"))
      (node (ref "T5") (pin "V29") (pinfunction "+VE_V29") (pintype "output"))
      (node (ref "T5") (pin "V3") (pinfunction "+VE_V3") (pintype "output"))
      (node (ref "T5") (pin "V30") (pinfunction "+VE_V30") (pintype "output"))
      (node (ref "T5") (pin "V31") (pinfunction "+VE_V31") (pintype "output"))
      (node (ref "T5") (pin "V4") (pinfunction "+VE_V4") (pintype "output"))
      (node (ref "T5") (pin "V5") (pinfunction "+VE_V5") (pintype "output"))
      (node (ref "T5") (pin "V6") (pinfunction "+VE_V6") (pintype "output"))
      (node (ref "T5") (pin "V7") (pinfunction "+VE_V7") (pintype "output"))
      (node (ref "T5") (pin "V8") (pinfunction "+VE_V8") (pintype "output"))
      (node (ref "T5") (pin "V9") (pinfunction "+VE_V9") (pintype "output"))
      (node (ref "T6") (pin "+VE") (pinfunction "+VE_+VE") (pintype "output"))
      (node (ref "T6") (pin "+VE_1") (pinfunction "+VE_+VE_1") (pintype "output"))
      (node (ref "T6") (pin "V1") (pinfunction "+VE_V1") (pintype "output"))
      (node (ref "T6") (pin "V10") (pinfunction "+VE_V10") (pintype "output"))
      (node (ref "T6") (pin "V11") (pinfunction "+VE_V11") (pintype "output"))
      (node (ref "T6") (pin "V12") (pinfunction "+VE_V12") (pintype "output"))
      (node (ref "T6") (pin "V13") (pinfunction "+VE_V13") (pintype "output"))
      (node (ref "T6") (pin "V14") (pinfunction "+VE_V14") (pintype "output"))
      (node (ref "T6") (pin "V15") (pinfunction "+VE_V15") (pintype "output"))
      (node (ref "T6") (pin "V16") (pinfunction "+VE_V16") (pintype "output"))
      (node (ref "T6") (pin "V17") (pinfunction "+VE_V17") (pintype "output"))
      (node (ref "T6") (pin "V18") (pinfunction "+VE_V18") (pintype "output"))
      (node (ref "T6") (pin "V19") (pinfunction "+VE_V19") (pintype "output"))
      (node (ref "T6") (pin "V20") (pinfunction "+VE_V20") (pintype "output"))
      (node (ref "T6") (pin "V21") (pinfunction "+VE_V21") (pintype "output"))
      (node (ref "T6") (pin "V22") (pinfunction "+VE_V22") (pintype "output"))
      (node (ref "T6") (pin "V23") (pinfunction "+VE_V23") (pintype "output"))
      (node (ref "T6") (pin "V24") (pinfunction "+VE_V24") (pintype "output"))
      (node (ref "T6") (pin "V25") (pinfunction "+VE_V25") (pintype "output"))
      (node (ref "T6") (pin "V26") (pinfunction "+VE_V26") (pintype "output"))
      (node (ref "T6") (pin "V27") (pinfunction "+VE_V27") (pintype "output"))
      (node (ref "T6") (pin "V28") (pinfunction "+VE_V28") (pintype "output"))
      (node (ref "T6") (pin "V29") (pinfunction "+VE_V29") (pintype "output"))
      (node (ref "T6") (pin "V3") (pinfunction "+VE_V3") (pintype "output"))
      (node (ref "T6") (pin "V30") (pinfunction "+VE_V30") (pintype "output"))
      (node (ref "T6") (pin "V31") (pinfunction "+VE_V31") (pintype "output"))
      (node (ref "T6") (pin "V4") (pinfunction "+VE_V4") (pintype "output"))
      (node (ref "T6") (pin "V5") (pinfunction "+VE_V5") (pintype "output"))
      (node (ref "T6") (pin "V6") (pinfunction "+VE_V6") (pintype "output"))
      (node (ref "T6") (pin "V7") (pinfunction "+VE_V7") (pintype "output"))
      (node (ref "T6") (pin "V8") (pinfunction "+VE_V8") (pintype "output"))
      (node (ref "T6") (pin "V9") (pinfunction "+VE_V9") (pintype "output"))
      (node (ref "T7") (pin "+VE") (pinfunction "+VE_+VE") (pintype "output"))
      (node (ref "T7") (pin "+VE_1") (pinfunction "+VE_+VE_1") (pintype "output"))
      (node (ref "T7") (pin "V1") (pinfunction "+VE_V1") (pintype "output"))
      (node (ref "T7") (pin "V10") (pinfunction "+VE_V10") (pintype "output"))
      (node (ref "T7") (pin "V11") (pinfunction "+VE_V11") (pintype "output"))
      (node (ref "T7") (pin "V12") (pinfunction "+VE_V12") (pintype "output"))
      (node (ref "T7") (pin "V13") (pinfunction "+VE_V13") (pintype "output"))
      (node (ref "T7") (pin "V14") (pinfunction "+VE_V14") (pintype "output"))
      (node (ref "T7") (pin "V15") (pinfunction "+VE_V15") (pintype "output"))
      (node (ref "T7") (pin "V16") (pinfunction "+VE_V16") (pintype "output"))
      (node (ref "T7") (pin "V17") (pinfunction "+VE_V17") (pintype "output"))
      (node (ref "T7") (pin "V18") (pinfunction "+VE_V18") (pintype "output"))
      (node (ref "T7") (pin "V19") (pinfunction "+VE_V19") (pintype "output"))
      (node (ref "T7") (pin "V20") (pinfunction "+VE_V20") (pintype "output"))
      (node (ref "T7") (pin "V21") (pinfunction "+VE_V21") (pintype "output"))
      (node (ref "T7") (pin "V22") (pinfunction "+VE_V22") (pintype "output"))
      (node (ref "T7") (pin "V23") (pinfunction "+VE_V23") (pintype "output"))
      (node (ref "T7") (pin "V24") (pinfunction "+VE_V24") (pintype "output"))
      (node (ref "T7") (pin "V25") (pinfunction "+VE_V25") (pintype "output"))
      (node (ref "T7") (pin "V26") (pinfunction "+VE_V26") (pintype "output"))
      (node (ref "T7") (pin "V27") (pinfunction "+VE_V27") (pintype "output"))
      (node (ref "T7") (pin "V28") (pinfunction "+VE_V28") (pintype "output"))
      (node (ref "T7") (pin "V29") (pinfunction "+VE_V29") (pintype "output"))
      (node (ref "T7") (pin "V3") (pinfunction "+VE_V3") (pintype "output"))
      (node (ref "T7") (pin "V30") (pinfunction "+VE_V30") (pintype "output"))
      (node (ref "T7") (pin "V31") (pinfunction "+VE_V31") (pintype "output"))
      (node (ref "T7") (pin "V4") (pinfunction "+VE_V4") (pintype "output"))
      (node (ref "T7") (pin "V5") (pinfunction "+VE_V5") (pintype "output"))
      (node (ref "T7") (pin "V6") (pinfunction "+VE_V6") (pintype "output"))
      (node (ref "T7") (pin "V7") (pinfunction "+VE_V7") (pintype "output"))
      (node (ref "T7") (pin "V8") (pinfunction "+VE_V8") (pintype "output"))
      (node (ref "T7") (pin "V9") (pinfunction "+VE_V9") (pintype "output"))
      (node (ref "U$1") (pin "V1") (pinfunction "+VE_V1") (pintype "bidirectional"))
      (node (ref "U$1") (pin "V3") (pinfunction "+VE_V3") (pintype "bidirectional"))
      (node (ref "U$1") (pin "V5") (pinfunction "+VE_V5") (pintype "bidirectional"))
      (node (ref "U$2") (pin "3") (pinfunction "S_3") (pintype "passive"))
      (node (ref "U$3") (pin "3") (pinfunction "S_3") (pintype "passive"))
    )
    (net (code "9") (name "V_IN") (class "Default")
      (node (ref "T1") (pin "+VE") (pinfunction "+VE_+VE") (pintype "bidirectional"))
      (node (ref "T1") (pin "+VE_1") (pinfunction "+VE_+VE_1") (pintype "bidirectional"))
      (node (ref "T1") (pin "V1") (pinfunction "+VE_V1") (pintype "bidirectional"))
      (node (ref "T1") (pin "V10") (pinfunction "+VE_V10") (pintype "bidirectional"))
      (node (ref "T1") (pin "V100") (pinfunction "+VE_V100") (pintype "bidirectional"))
      (node (ref "T1") (pin "V101") (pinfunction "+VE_V101") (pintype "bidirectional"))
      (node (ref "T1") (pin "V102") (pinfunction "+VE_V102") (pintype "bidirectional"))
      (node (ref "T1") (pin "V103") (pinfunction "+VE_V103") (pintype "bidirectional"))
      (node (ref "T1") (pin "V104") (pinfunction "+VE_V104") (pintype "bidirectional"))
      (node (ref "T1") (pin "V105") (pinfunction "+VE_V105") (pintype "bidirectional"))
      (node (ref "T1") (pin "V106") (pinfunction "+VE_V106") (pintype "bidirectional"))
      (node (ref "T1") (pin "V107") (pinfunction "+VE_V107") (pintype "bidirectional"))
      (node (ref "T1") (pin "V108") (pinfunction "+VE_V108") (pintype "bidirectional"))
      (node (ref "T1") (pin "V11") (pinfunction "+VE_V11") (pintype "bidirectional"))
      (node (ref "T1") (pin "V12") (pinfunction "+VE_V12") (pintype "bidirectional"))
      (node (ref "T1") (pin "V120") (pinfunction "+VE_V120") (pintype "bidirectional"))
      (node (ref "T1") (pin "V13") (pinfunction "+VE_V13") (pintype "bidirectional"))
      (node (ref "T1") (pin "V132") (pinfunction "+VE_V132") (pintype "bidirectional"))
      (node (ref "T1") (pin "V14") (pinfunction "+VE_V14") (pintype "bidirectional"))
      (node (ref "T1") (pin "V144") (pinfunction "+VE_V144") (pintype "bidirectional"))
      (node (ref "T1") (pin "V15") (pinfunction "+VE_V15") (pintype "bidirectional"))
      (node (ref "T1") (pin "V156") (pinfunction "+VE_V156") (pintype "bidirectional"))
      (node (ref "T1") (pin "V16") (pinfunction "+VE_V16") (pintype "bidirectional"))
      (node (ref "T1") (pin "V168") (pinfunction "+VE_V168") (pintype "bidirectional"))
      (node (ref "T1") (pin "V17") (pinfunction "+VE_V17") (pintype "bidirectional"))
      (node (ref "T1") (pin "V18") (pinfunction "+VE_V18") (pintype "bidirectional"))
      (node (ref "T1") (pin "V180") (pinfunction "+VE_V180") (pintype "bidirectional"))
      (node (ref "T1") (pin "V19") (pinfunction "+VE_V19") (pintype "bidirectional"))
      (node (ref "T1") (pin "V192") (pinfunction "+VE_V192") (pintype "bidirectional"))
      (node (ref "T1") (pin "V2") (pinfunction "+VE_V2") (pintype "bidirectional"))
      (node (ref "T1") (pin "V20") (pinfunction "+VE_V20") (pintype "bidirectional"))
      (node (ref "T1") (pin "V204") (pinfunction "+VE_V204") (pintype "bidirectional"))
      (node (ref "T1") (pin "V205") (pinfunction "+VE_V205") (pintype "bidirectional"))
      (node (ref "T1") (pin "V206") (pinfunction "+VE_V206") (pintype "bidirectional"))
      (node (ref "T1") (pin "V207") (pinfunction "+VE_V207") (pintype "bidirectional"))
      (node (ref "T1") (pin "V208") (pinfunction "+VE_V208") (pintype "bidirectional"))
      (node (ref "T1") (pin "V209") (pinfunction "+VE_V209") (pintype "bidirectional"))
      (node (ref "T1") (pin "V21") (pinfunction "+VE_V21") (pintype "bidirectional"))
      (node (ref "T1") (pin "V210") (pinfunction "+VE_V210") (pintype "bidirectional"))
      (node (ref "T1") (pin "V211") (pinfunction "+VE_V211") (pintype "bidirectional"))
      (node (ref "T1") (pin "V212") (pinfunction "+VE_V212") (pintype "bidirectional"))
      (node (ref "T1") (pin "V213") (pinfunction "+VE_V213") (pintype "bidirectional"))
      (node (ref "T1") (pin "V214") (pinfunction "+VE_V214") (pintype "bidirectional"))
      (node (ref "T1") (pin "V215") (pinfunction "+VE_V215") (pintype "bidirectional"))
      (node (ref "T1") (pin "V216") (pinfunction "+VE_V216") (pintype "bidirectional"))
      (node (ref "T1") (pin "V217") (pinfunction "+VE_V217") (pintype "bidirectional"))
      (node (ref "T1") (pin "V218") (pinfunction "+VE_V218") (pintype "bidirectional"))
      (node (ref "T1") (pin "V219") (pinfunction "+VE_V219") (pintype "bidirectional"))
      (node (ref "T1") (pin "V22") (pinfunction "+VE_V22") (pintype "bidirectional"))
      (node (ref "T1") (pin "V220") (pinfunction "+VE_V220") (pintype "bidirectional"))
      (node (ref "T1") (pin "V221") (pinfunction "+VE_V221") (pintype "bidirectional"))
      (node (ref "T1") (pin "V222") (pinfunction "+VE_V222") (pintype "bidirectional"))
      (node (ref "T1") (pin "V223") (pinfunction "+VE_V223") (pintype "bidirectional"))
      (node (ref "T1") (pin "V224") (pinfunction "+VE_V224") (pintype "bidirectional"))
      (node (ref "T1") (pin "V225") (pinfunction "+VE_V225") (pintype "bidirectional"))
      (node (ref "T1") (pin "V226") (pinfunction "+VE_V226") (pintype "bidirectional"))
      (node (ref "T1") (pin "V227") (pinfunction "+VE_V227") (pintype "bidirectional"))
      (node (ref "T1") (pin "V228") (pinfunction "+VE_V228") (pintype "bidirectional"))
      (node (ref "T1") (pin "V229") (pinfunction "+VE_V229") (pintype "bidirectional"))
      (node (ref "T1") (pin "V23") (pinfunction "+VE_V23") (pintype "bidirectional"))
      (node (ref "T1") (pin "V230") (pinfunction "+VE_V230") (pintype "bidirectional"))
      (node (ref "T1") (pin "V231") (pinfunction "+VE_V231") (pintype "bidirectional"))
      (node (ref "T1") (pin "V24") (pinfunction "+VE_V24") (pintype "bidirectional"))
      (node (ref "T1") (pin "V25") (pinfunction "+VE_V25") (pintype "bidirectional"))
      (node (ref "T1") (pin "V26") (pinfunction "+VE_V26") (pintype "bidirectional"))
      (node (ref "T1") (pin "V27") (pinfunction "+VE_V27") (pintype "bidirectional"))
      (node (ref "T1") (pin "V28") (pinfunction "+VE_V28") (pintype "bidirectional"))
      (node (ref "T1") (pin "V29") (pinfunction "+VE_V29") (pintype "bidirectional"))
      (node (ref "T1") (pin "V3") (pinfunction "+VE_V3") (pintype "bidirectional"))
      (node (ref "T1") (pin "V30") (pinfunction "+VE_V30") (pintype "bidirectional"))
      (node (ref "T1") (pin "V31") (pinfunction "+VE_V31") (pintype "bidirectional"))
      (node (ref "T1") (pin "V32") (pinfunction "+VE_V32") (pintype "bidirectional"))
      (node (ref "T1") (pin "V33") (pinfunction "+VE_V33") (pintype "bidirectional"))
      (node (ref "T1") (pin "V34") (pinfunction "+VE_V34") (pintype "bidirectional"))
      (node (ref "T1") (pin "V35") (pinfunction "+VE_V35") (pintype "bidirectional"))
      (node (ref "T1") (pin "V36") (pinfunction "+VE_V36") (pintype "bidirectional"))
      (node (ref "T1") (pin "V37") (pinfunction "+VE_V37") (pintype "bidirectional"))
      (node (ref "T1") (pin "V38") (pinfunction "+VE_V38") (pintype "bidirectional"))
      (node (ref "T1") (pin "V39") (pinfunction "+VE_V39") (pintype "bidirectional"))
      (node (ref "T1") (pin "V4") (pinfunction "+VE_V4") (pintype "bidirectional"))
      (node (ref "T1") (pin "V40") (pinfunction "+VE_V40") (pintype "bidirectional"))
      (node (ref "T1") (pin "V41") (pinfunction "+VE_V41") (pintype "bidirectional"))
      (node (ref "T1") (pin "V42") (pinfunction "+VE_V42") (pintype "bidirectional"))
      (node (ref "T1") (pin "V43") (pinfunction "+VE_V43") (pintype "bidirectional"))
      (node (ref "T1") (pin "V44") (pinfunction "+VE_V44") (pintype "bidirectional"))
      (node (ref "T1") (pin "V45") (pinfunction "+VE_V45") (pintype "bidirectional"))
      (node (ref "T1") (pin "V46") (pinfunction "+VE_V46") (pintype "bidirectional"))
      (node (ref "T1") (pin "V47") (pinfunction "+VE_V47") (pintype "bidirectional"))
      (node (ref "T1") (pin "V48") (pinfunction "+VE_V48") (pintype "bidirectional"))
      (node (ref "T1") (pin "V49") (pinfunction "+VE_V49") (pintype "bidirectional"))
      (node (ref "T1") (pin "V5") (pinfunction "+VE_V5") (pintype "bidirectional"))
      (node (ref "T1") (pin "V50") (pinfunction "+VE_V50") (pintype "bidirectional"))
      (node (ref "T1") (pin "V51") (pinfunction "+VE_V51") (pintype "bidirectional"))
      (node (ref "T1") (pin "V52") (pinfunction "+VE_V52") (pintype "bidirectional"))
      (node (ref "T1") (pin "V53") (pinfunction "+VE_V53") (pintype "bidirectional"))
      (node (ref "T1") (pin "V54") (pinfunction "+VE_V54") (pintype "bidirectional"))
      (node (ref "T1") (pin "V55") (pinfunction "+VE_V55") (pintype "bidirectional"))
      (node (ref "T1") (pin "V56") (pinfunction "+VE_V56") (pintype "bidirectional"))
      (node (ref "T1") (pin "V57") (pinfunction "+VE_V57") (pintype "bidirectional"))
      (node (ref "T1") (pin "V58") (pinfunction "+VE_V58") (pintype "bidirectional"))
      (node (ref "T1") (pin "V59") (pinfunction "+VE_V59") (pintype "bidirectional"))
      (node (ref "T1") (pin "V6") (pinfunction "+VE_V6") (pintype "bidirectional"))
      (node (ref "T1") (pin "V60") (pinfunction "+VE_V60") (pintype "bidirectional"))
      (node (ref "T1") (pin "V61") (pinfunction "+VE_V61") (pintype "bidirectional"))
      (node (ref "T1") (pin "V62") (pinfunction "+VE_V62") (pintype "bidirectional"))
      (node (ref "T1") (pin "V63") (pinfunction "+VE_V63") (pintype "bidirectional"))
      (node (ref "T1") (pin "V64") (pinfunction "+VE_V64") (pintype "bidirectional"))
      (node (ref "T1") (pin "V65") (pinfunction "+VE_V65") (pintype "bidirectional"))
      (node (ref "T1") (pin "V66") (pinfunction "+VE_V66") (pintype "bidirectional"))
      (node (ref "T1") (pin "V67") (pinfunction "+VE_V67") (pintype "bidirectional"))
      (node (ref "T1") (pin "V68") (pinfunction "+VE_V68") (pintype "bidirectional"))
      (node (ref "T1") (pin "V69") (pinfunction "+VE_V69") (pintype "bidirectional"))
      (node (ref "T1") (pin "V7") (pinfunction "+VE_V7") (pintype "bidirectional"))
      (node (ref "T1") (pin "V70") (pinfunction "+VE_V70") (pintype "bidirectional"))
      (node (ref "T1") (pin "V71") (pinfunction "+VE_V71") (pintype "bidirectional"))
      (node (ref "T1") (pin "V72") (pinfunction "+VE_V72") (pintype "bidirectional"))
      (node (ref "T1") (pin "V73") (pinfunction "+VE_V73") (pintype "bidirectional"))
      (node (ref "T1") (pin "V74") (pinfunction "+VE_V74") (pintype "bidirectional"))
      (node (ref "T1") (pin "V75") (pinfunction "+VE_V75") (pintype "bidirectional"))
      (node (ref "T1") (pin "V76") (pinfunction "+VE_V76") (pintype "bidirectional"))
      (node (ref "T1") (pin "V77") (pinfunction "+VE_V77") (pintype "bidirectional"))
      (node (ref "T1") (pin "V78") (pinfunction "+VE_V78") (pintype "bidirectional"))
      (node (ref "T1") (pin "V79") (pinfunction "+VE_V79") (pintype "bidirectional"))
      (node (ref "T1") (pin "V8") (pinfunction "+VE_V8") (pintype "bidirectional"))
      (node (ref "T1") (pin "V80") (pinfunction "+VE_V80") (pintype "bidirectional"))
      (node (ref "T1") (pin "V81") (pinfunction "+VE_V81") (pintype "bidirectional"))
      (node (ref "T1") (pin "V82") (pinfunction "+VE_V82") (pintype "bidirectional"))
      (node (ref "T1") (pin "V83") (pinfunction "+VE_V83") (pintype "bidirectional"))
      (node (ref "T1") (pin "V84") (pinfunction "+VE_V84") (pintype "bidirectional"))
      (node (ref "T1") (pin "V85") (pinfunction "+VE_V85") (pintype "bidirectional"))
      (node (ref "T1") (pin "V86") (pinfunction "+VE_V86") (pintype "bidirectional"))
      (node (ref "T1") (pin "V87") (pinfunction "+VE_V87") (pintype "bidirectional"))
      (node (ref "T1") (pin "V88") (pinfunction "+VE_V88") (pintype "bidirectional"))
      (node (ref "T1") (pin "V89") (pinfunction "+VE_V89") (pintype "bidirectional"))
      (node (ref "T1") (pin "V9") (pinfunction "+VE_V9") (pintype "bidirectional"))
      (node (ref "T1") (pin "V90") (pinfunction "+VE_V90") (pintype "bidirectional"))
      (node (ref "T1") (pin "V91") (pinfunction "+VE_V91") (pintype "bidirectional"))
      (node (ref "T1") (pin "V92") (pinfunction "+VE_V92") (pintype "bidirectional"))
      (node (ref "T1") (pin "V93") (pinfunction "+VE_V93") (pintype "bidirectional"))
      (node (ref "T1") (pin "V94") (pinfunction "+VE_V94") (pintype "bidirectional"))
      (node (ref "T1") (pin "V95") (pinfunction "+VE_V95") (pintype "bidirectional"))
      (node (ref "T1") (pin "V96") (pinfunction "+VE_V96") (pintype "bidirectional"))
      (node (ref "T1") (pin "V97") (pinfunction "+VE_V97") (pintype "bidirectional"))
      (node (ref "T1") (pin "V98") (pinfunction "+VE_V98") (pintype "bidirectional"))
      (node (ref "T1") (pin "V99") (pinfunction "+VE_V99") (pintype "bidirectional"))
      (node (ref "U$2") (pin "2") (pinfunction "D_2") (pintype "passive"))
      (node (ref "U$3") (pin "2") (pinfunction "D_2") (pintype "passive"))
    )
    (net (code "10") (name "unconnected-(J2-Pad2)") (class "Default")
      (node (ref "J2") (pin "2") (pinfunction "2_2") (pintype "passive"))
    )
    (net (code "11") (name "unconnected-(J2-Pad4)") (class "Default")
      (node (ref "J2") (pin "4") (pinfunction "4_4") (pintype "passive"))
    )
    (net (code "12") (name "unconnected-(J2-Pad5)") (class "Default")
      (node (ref "J2") (pin "5") (pinfunction "5_5") (pintype "passive"))
    )
    (net (code "13") (name "unconnected-(J2-Pad6)") (class "Default")
      (node (ref "J2") (pin "6") (pinfunction "6_6") (pintype "passive"))
    )
    (net (code "14") (name "unconnected-(J2-Pad7)") (class "Default")
      (node (ref "J2") (pin "7") (pinfunction "7_7") (pintype "passive"))
    )
  )
)
